# Cording.net
KiCad netlist of a schematic drawn in Altium Designer
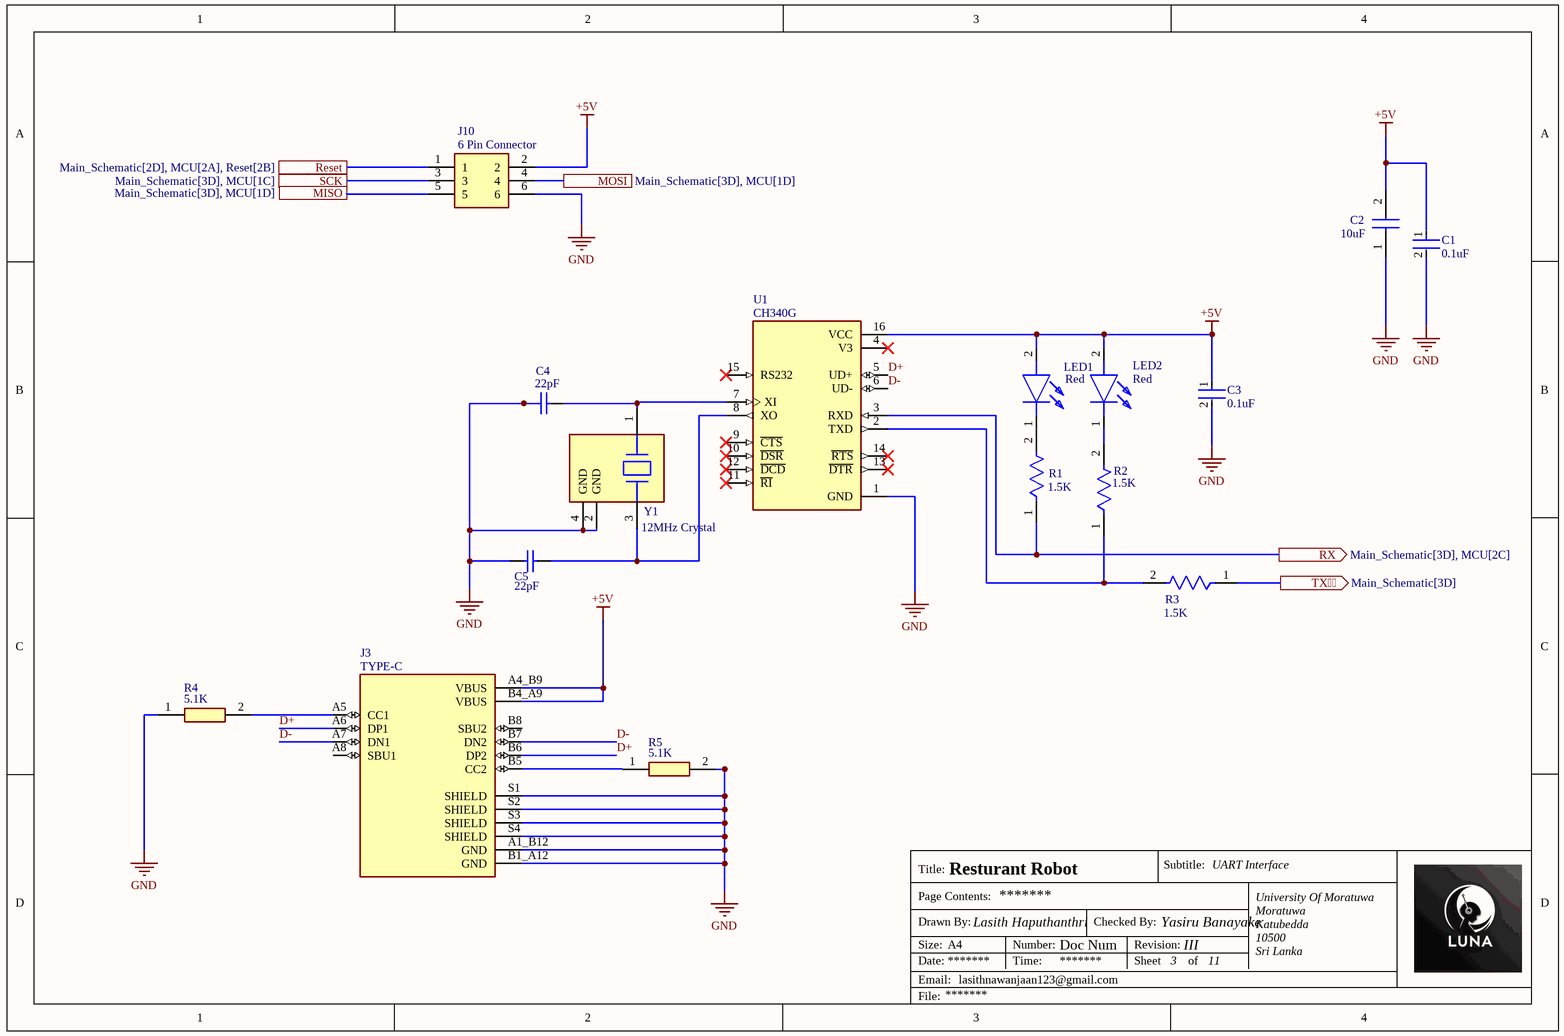
[diagram p0: Cording.SchDoc]

(export (version "E")
  (design (tool "Eeschema 10.0.6"))
  (components
    (comp (ref "C1")
      (value "0.1uF")
      (footprint "FP-CC0603-DA-MFG")
      (description "CC0603KRX7R9BB104 CAP CER 0.1UF 50V X7R 0603")
      (fields (field (name "MANUFACTURER") "YAGEO") (field (name "VOLTAGE") "50 V"))
      (libsource (lib "Altium Content Vault") (part "11868f565c42a9108669ba33697ecf6"))
    )
    (comp (ref "C2")
      (value "10uF")
      (footprint "SamacSys:CAPC1608X90N")
      (description "CL10A106KP8NNNC Capacitor")
      (fields
        (field (name "MANUFACTURER_PART_NUMBER") "CL10A106KP8NNNC")
        (field (name "MOUSER PART NUMBER") "187-CL10A106KP8NNNC")
      )
      (libsource (lib "*") (part "CL10A106KP8NNNC"))
    )
    (comp (ref "C3")
      (value "0.1uF")
      (footprint "FP-CC0603-DA-MFG")
      (description "CC0603KRX7R9BB104 CAP CER 0.1UF 50V X7R 0603")
      (fields (field (name "MANUFACTURER") "YAGEO") (field (name "VOLTAGE") "50 V"))
      (libsource (lib "Altium Content Vault") (part "11868f565c42a9108669ba33697ecf6"))
    )
    (comp (ref "C4")
      (value "22pF")
      (footprint "CAPC1608X90X40LL10T20")
      (libsource (lib "Altium Content Vault") (part "CAP-NP-2"))
    )
    (comp (ref "C5")
      (value "22pF")
      (footprint "CAPC1608X90X40LL10T20")
      (libsource (lib "Altium Content Vault") (part "CAP-NP-2"))
    )
    (comp (ref "J3")
      (value "TYPE-C")
      (footprint "HRO_TYPE-C-31-M-12")
      (description "TYPE-C-31-M-12 USB Connectors 24 Receptacle 1 8.94*7.3mm RoHS")
      (fields (field (name "MF") "HRO Electronics Co., Ltd.") (field (name "MP") "TYPE-C-31-M-12"))
      (libsource (lib "TYPE-C-31-M-12") (part "TYPE-C-31-M-12"))
    )
    (comp (ref "J10")
      (value "6 Pin Connector")
      (footprint "SamacSys:HDRV6W64P254_2X3_762X508X868P")
      (description "Connector")
      (fields
        (field (name "MANUFACTURER_PART_NUMBER") "M20-9980346")
        (field (name "MOUSER PART NUMBER") "855-M20-9980346")
      )
      (libsource (lib "*") (part "M20-9980346"))
    )
    (comp (ref "LED1")
      (value "Red")
      (footprint "SamacSys:LEDC1608X55N")
      (description "LED")
      (fields
        (field (name "MANUFACTURER_PART_NUMBER") "LTST-C191KRKT")
        (field (name "MOUSER PART NUMBER") "859-LTST-C191KRKT")
      )
      (libsource (lib "*") (part "LTST-C191KRKT"))
    )
    (comp (ref "LED2")
      (value "Red")
      (footprint "SamacSys:LEDC1608X55N")
      (description "LED")
      (fields
        (field (name "MANUFACTURER_PART_NUMBER") "LTST-C191KRKT")
        (field (name "MOUSER PART NUMBER") "859-LTST-C191KRKT")
      )
      (libsource (lib "*") (part "LTST-C191KRKT"))
    )
    (comp (ref "R1")
      (value "1.5K")
      (footprint "FP-AF0603-IPC_B")
      (description "AF0603FR-071K5L Anti-Sulfurated Chip Resistors Automotive Grade 1.5kΩ 1% 100ppm/°C 0603")
      (fields (field (name "TOLERANCE") "1%"))
      (libsource (lib "Altium Content Vault") (part "1029c3af85768c4190bb7ad29bc67b5"))
    )
    (comp (ref "R2")
      (value "1.5K")
      (footprint "FP-AF0603-IPC_B")
      (description "AF0603FR-071K5L Anti-Sulfurated Chip Resistors Automotive Grade 1.5kΩ 1% 100ppm/°C 0603")
      (fields (field (name "TOLERANCE") "1%"))
      (libsource (lib "Altium Content Vault") (part "1029c3af85768c4190bb7ad29bc67b5"))
    )
    (comp (ref "R3")
      (value "1.5K")
      (footprint "FP-AF0603-IPC_B")
      (description "AF0603FR-071K5L Anti-Sulfurated Chip Resistors Automotive Grade 1.5kΩ 1% 100ppm/°C 0603")
      (fields (field (name "TOLERANCE") "1%"))
      (libsource (lib "Altium Content Vault") (part "1029c3af85768c4190bb7ad29bc67b5"))
    )
    (comp (ref "R4")
      (value "5.1K")
      (footprint "SamacSys:RESC1608X55N")
      (description "0603WAF5101T5E")
      (libsource (lib "*") (part "0603WAF5101T5E"))
    )
    (comp (ref "R5")
      (value "5.1K")
      (footprint "SamacSys:RESC1608X55N")
      (description "0603WAF5101T5E Resistor")
      (fields (field (name "MANUFACTURER_PART_NUMBER") "0603WAF5101T5E"))
      (libsource (lib "*") (part "0603WAF5101T5E"))
    )
    (comp (ref "U1")
      (value "CH340G")
      (footprint "SOIC127P600X180-16N")
      (description "USB Interface Integrated Circuit")
      (fields (field (name "MP") "Ch340G") (field (name "MF") "WCH"))
      (libsource (lib "CH340G") (part "CH340G"))
    )
    (comp (ref "Y1")
      (value "12MHz Crystal")
      (footprint "FP-ABM8G-MFG")
      (fields (field (name "TOLERANCE") "20ppm"))
      (libsource (lib "Altium Content Vault") (part "48e526d86b7f2615d98721063c72f49"))
    )
  )
  (nets
    (net (code "1") (name "+5V") (class "Default")
      (node (ref "C1") (pin "1") (pinfunction "1_1") (pintype "passive"))
      (node (ref "C2") (pin "2") (pinfunction "2_2") (pintype "passive"))
      (node (ref "C3") (pin "1") (pinfunction "1_1") (pintype "passive"))
      (node (ref "J10") (pin "2") (pinfunction "2_2") (pintype "passive"))
      (node (ref "J3") (pin "A4_B9") (pinfunction "VBUS_A4_B9") (pintype "power_in"))
      (node (ref "J3") (pin "B4_A9") (pinfunction "VBUS_B4_A9") (pintype "power_in"))
      (node (ref "LED1") (pin "2") (pinfunction "A_2") (pintype "passive"))
      (node (ref "LED2") (pin "2") (pinfunction "A_2") (pintype "passive"))
      (node (ref "U1") (pin "16") (pinfunction "VCC_16") (pintype "power_in"))
    )
    (net (code "2") (name "/D+") (class "Default")
      (node (ref "J3") (pin "A6") (pinfunction "DP1_A6") (pintype "bidirectional"))
      (node (ref "J3") (pin "B6") (pinfunction "DP2_B6") (pintype "bidirectional"))
      (node (ref "U1") (pin "5") (pinfunction "UD+_5") (pintype "bidirectional"))
    )
    (net (code "3") (name "/D-") (class "Default")
      (node (ref "J3") (pin "A7") (pinfunction "DN1_A7") (pintype "bidirectional"))
      (node (ref "J3") (pin "B7") (pinfunction "DN2_B7") (pintype "bidirectional"))
      (node (ref "U1") (pin "6") (pinfunction "UD-_6") (pintype "bidirectional"))
    )
    (net (code "4") (name "/MISO") (class "Default")
      (node (ref "J10") (pin "5") (pinfunction "5_5") (pintype "passive"))
    )
    (net (code "5") (name "/MOSI") (class "Default")
      (node (ref "J10") (pin "4") (pinfunction "4_4") (pintype "passive"))
    )
    (net (code "6") (name "/RX") (class "Default")
      (node (ref "R1") (pin "1") (pinfunction "1_1") (pintype "passive"))
      (node (ref "U1") (pin "3") (pinfunction "RXD_3") (pintype "input"))
    )
    (net (code "7") (name "/Reset") (class "Default")
      (node (ref "J10") (pin "1") (pinfunction "1_1") (pintype "passive"))
    )
    (net (code "8") (name "/SCK") (class "Default")
      (node (ref "J10") (pin "3") (pinfunction "3_3") (pintype "passive"))
    )
    (net (code "9") (name "/TX") (class "Default")
      (node (ref "R3") (pin "1") (pinfunction "1_1") (pintype "passive"))
    )
    (net (code "10") (name "GND") (class "Default")
      (node (ref "C1") (pin "2") (pinfunction "2_2") (pintype "passive"))
      (node (ref "C2") (pin "1") (pinfunction "1_1") (pintype "passive"))
      (node (ref "C3") (pin "2") (pinfunction "2_2") (pintype "passive"))
      (node (ref "C4") (pin "1") (pinfunction "1_1") (pintype "passive"))
      (node (ref "C5") (pin "1") (pinfunction "1_1") (pintype "passive"))
      (node (ref "J10") (pin "6") (pinfunction "6_6") (pintype "passive"))
      (node (ref "J3") (pin "A1_B12") (pinfunction "GND_A1_B12") (pintype "power_in"))
      (node (ref "J3") (pin "B1_A12") (pinfunction "GND_B1_A12") (pintype "power_in"))
      (node (ref "J3") (pin "S1") (pinfunction "SHIELD_S1") (pintype "passive"))
      (node (ref "J3") (pin "S2") (pinfunction "SHIELD_S2") (pintype "passive"))
      (node (ref "J3") (pin "S3") (pinfunction "SHIELD_S3") (pintype "passive"))
      (node (ref "J3") (pin "S4") (pinfunction "SHIELD_S4") (pintype "passive"))
      (node (ref "R4") (pin "1") (pinfunction "1_1") (pintype "passive"))
      (node (ref "R5") (pin "2") (pinfunction "2_2") (pintype "passive"))
      (node (ref "U1") (pin "1") (pinfunction "GND_1") (pintype "power_in"))
      (node (ref "Y1") (pin "2") (pinfunction "GND_2") (pintype "power_in"))
      (node (ref "Y1") (pin "4") (pinfunction "GND_4") (pintype "power_in"))
    )
    (net (code "11") (name "Net-(J3-CC1)") (class "Default")
      (node (ref "J3") (pin "A5") (pinfunction "CC1_A5") (pintype "bidirectional"))
      (node (ref "R4") (pin "2") (pinfunction "2_2") (pintype "passive"))
    )
    (net (code "12") (name "Net-(J3-CC2)") (class "Default")
      (node (ref "J3") (pin "B5") (pinfunction "CC2_B5") (pintype "bidirectional"))
      (node (ref "R5") (pin "1") (pinfunction "1_1") (pintype "passive"))
    )
    (net (code "13") (name "Net-(LED1-K)") (class "Default")
      (node (ref "LED1") (pin "1") (pinfunction "K_1") (pintype "passive"))
      (node (ref "R1") (pin "2") (pinfunction "2_2") (pintype "passive"))
    )
    (net (code "14") (name "Net-(LED2-K)") (class "Default")
      (node (ref "LED2") (pin "1") (pinfunction "K_1") (pintype "passive"))
      (node (ref "R2") (pin "2") (pinfunction "2_2") (pintype "passive"))
    )
    (net (code "15") (name "Net-(U1-TXD)") (class "Default")
      (node (ref "R2") (pin "1") (pinfunction "1_1") (pintype "passive"))
      (node (ref "R3") (pin "2") (pinfunction "2_2") (pintype "passive"))
      (node (ref "U1") (pin "2") (pinfunction "TXD_2") (pintype "output"))
    )
    (net (code "16") (name "Net-(U1-XI)") (class "Default")
      (node (ref "C4") (pin "2") (pinfunction "2_2") (pintype "passive"))
      (node (ref "U1") (pin "7") (pinfunction "XI_7") (pintype "input"))
      (node (ref "Y1") (pin "1") (pinfunction "1_1") (pintype "passive"))
    )
    (net (code "17") (name "Net-(U1-XO)") (class "Default")
      (node (ref "C5") (pin "2") (pinfunction "2_2") (pintype "passive"))
      (node (ref "U1") (pin "8") (pinfunction "XO_8") (pintype "output"))
      (node (ref "Y1") (pin "3") (pinfunction "3_3") (pintype "passive"))
    )
    (net (code "18") (name "unconnected-(J3-SBU1-PadA8)") (class "Default")
      (node (ref "J3") (pin "A8") (pinfunction "SBU1_A8") (pintype "bidirectional"))
    )
    (net (code "19") (name "unconnected-(J3-SBU2-PadB8)") (class "Default")
      (node (ref "J3") (pin "B8") (pinfunction "SBU2_B8") (pintype "bidirectional"))
    )
    (net (code "20") (name "unconnected-(U1-RS232-Pad15)") (class "Default")
      (node (ref "U1") (pin "15") (pinfunction "RS232_15") (pintype "input+no_connect"))
    )
    (net (code "21") (name "unconnected-(U1-V3-Pad4)") (class "Default")
      (node (ref "U1") (pin "4") (pinfunction "V3_4") (pintype "power_in+no_connect"))
    )
    (net (code "22") (name "unconnected-(U1-~{CTS}-Pad9)") (class "Default")
      (node (ref "U1") (pin "9") (pinfunction "~{CTS}_9") (pintype "input+no_connect"))
    )
    (net (code "23") (name "unconnected-(U1-~{DCD}-Pad12)") (class "Default")
      (node (ref "U1") (pin "12") (pinfunction "~{DCD}_12") (pintype "input+no_connect"))
    )
    (net (code "24") (name "unconnected-(U1-~{DSR}-Pad10)") (class "Default")
      (node (ref "U1") (pin "10") (pinfunction "~{DSR}_10") (pintype "input+no_connect"))
    )
    (net (code "25") (name "unconnected-(U1-~{DTR}-Pad13)") (class "Default")
      (node (ref "U1") (pin "13") (pinfunction "~{DTR}_13") (pintype "output+no_connect"))
    )
    (net (code "26") (name "unconnected-(U1-~{RI}-Pad11)") (class "Default")
      (node (ref "U1") (pin "11") (pinfunction "~{RI}_11") (pintype "input+no_connect"))
    )
    (net (code "27") (name "unconnected-(U1-~{RTS}-Pad14)") (class "Default")
      (node (ref "U1") (pin "14") (pinfunction "~{RTS}_14") (pintype "output+no_connect"))
    )
  )
)
